# SCH_fateh_pre-charge_circuit0_draft1.net
KiCad netlist of a schematic drawn in EasyEDA
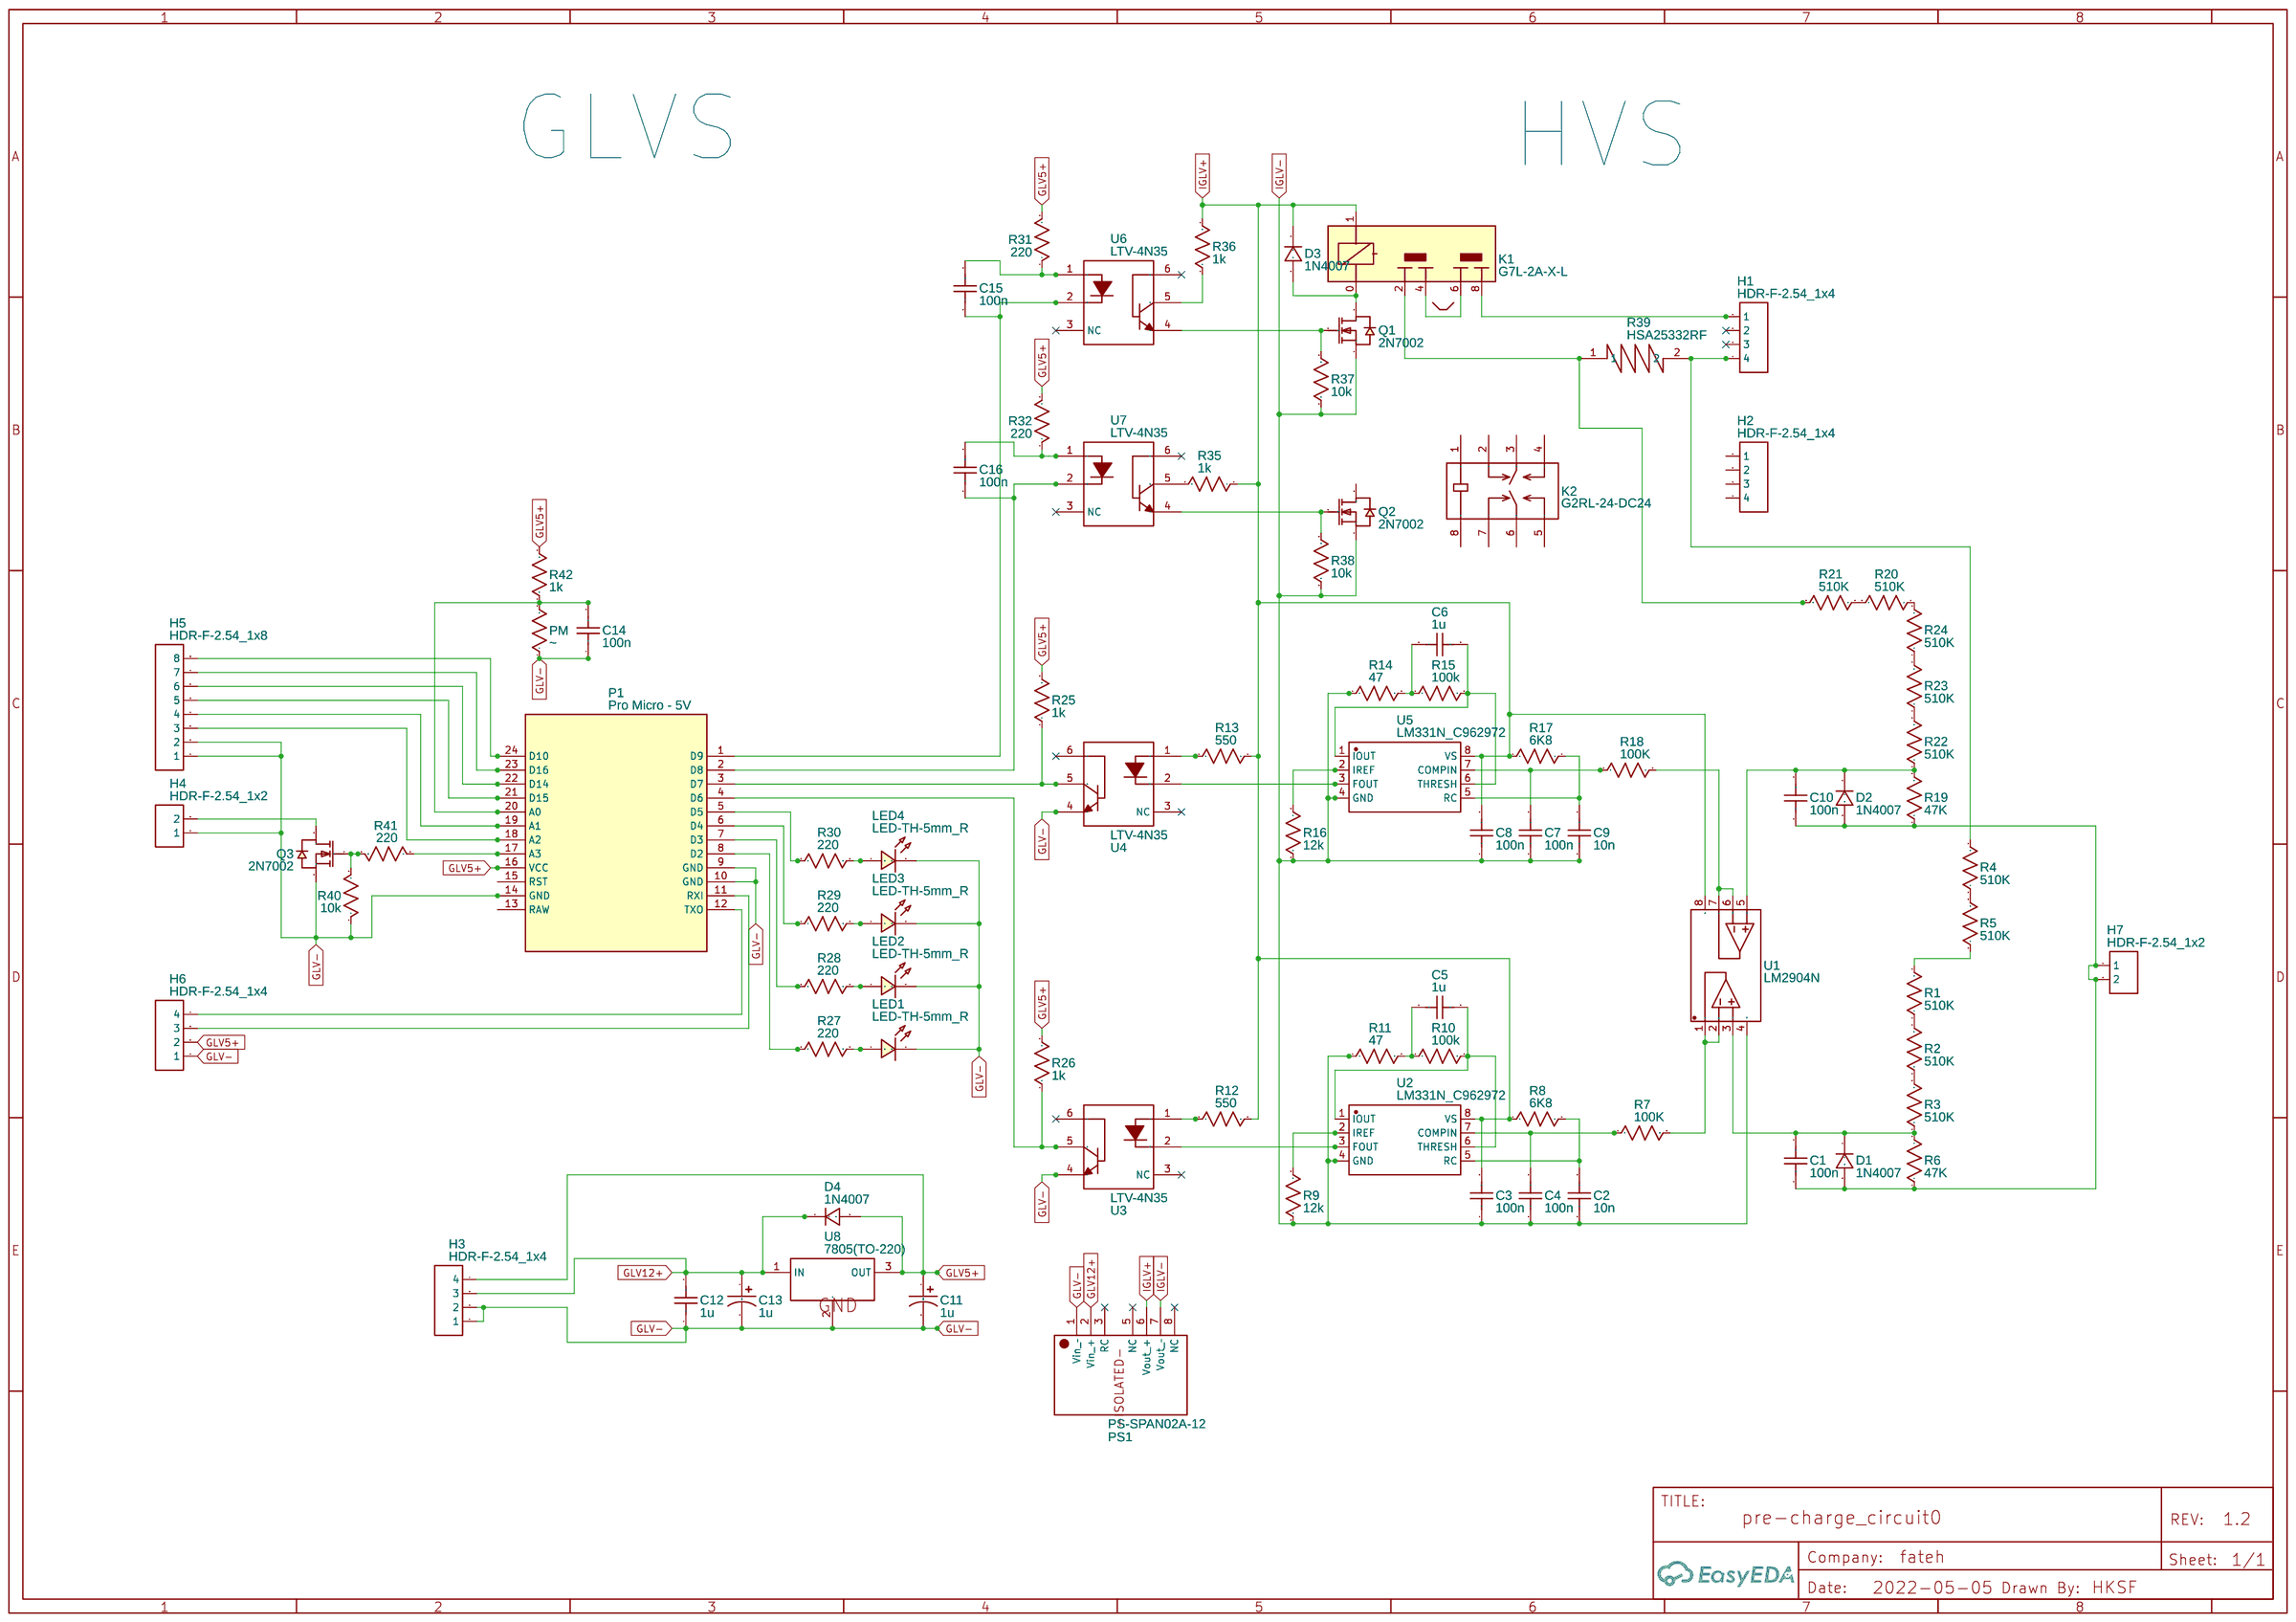
[diagram p0: schematic sheet]

(export (version "E")
  (design (tool "Eeschema 10.0.6"))
  (components
    (comp (ref "C1") (value "100n") (libsource (lib "") (part "C_RAD-0.1_US")))
    (comp (ref "C2") (value "10n") (libsource (lib "") (part "C_RAD-0.1_US")))
    (comp (ref "C3") (value "100n") (libsource (lib "") (part "C_RAD-0.1_US")))
    (comp (ref "C4") (value "100n") (libsource (lib "") (part "C_RAD-0.1_US")))
    (comp (ref "C5") (value "1u") (libsource (lib "") (part "C_RAD-0.1_US_1")))
    (comp (ref "C6") (value "1u") (libsource (lib "") (part "C_RAD-0.1_US_1")))
    (comp (ref "C7") (value "100n") (libsource (lib "") (part "C_RAD-0.1_US")))
    (comp (ref "C8") (value "100n") (libsource (lib "") (part "C_RAD-0.1_US")))
    (comp (ref "C9") (value "10n") (libsource (lib "") (part "C_RAD-0.1_US")))
    (comp (ref "C10") (value "100n") (libsource (lib "") (part "C_RAD-0.1_US")))
    (comp (ref "C11") (value "1u") (libsource (lib "") (part "CE_TH_D12.5×F5.0_US")))
    (comp (ref "C12") (value "1u") (libsource (lib "") (part "C_RAD-0.1_US")))
    (comp (ref "C13") (value "1u") (libsource (lib "") (part "CE_TH_D12.5×F5.0_US")))
    (comp (ref "C14") (value "100n") (libsource (lib "") (part "C_RAD-0.1_US")))
    (comp (ref "C15") (value "100n") (libsource (lib "") (part "C_RAD-0.1_US")))
    (comp (ref "C16") (value "100n") (libsource (lib "") (part "C_RAD-0.1_US")))
    (comp (ref "D1")
      (value "1N4007")
      (fields (field (name "BOM_Supplier Part") "C106903"))
      (libsource (lib "") (part "1N4007"))
    )
    (comp (ref "D2")
      (value "1N4007")
      (fields (field (name "BOM_Supplier Part") "C106903"))
      (libsource (lib "") (part "1N4007"))
    )
    (comp (ref "D3")
      (value "1N4007")
      (fields (field (name "BOM_Supplier Part") "C106903"))
      (libsource (lib "") (part "1N4007"))
    )
    (comp (ref "D4")
      (value "1N4007")
      (fields (field (name "BOM_Supplier Part") "C106903"))
      (libsource (lib "") (part "1N4007_1"))
    )
    (comp (ref "H1")
      (value "HDR-F-2.54_1x4")
      (fields (field (name "BOM_Supplier Part") "C225501"))
      (libsource (lib "") (part "HDR-F-2.54_1x4"))
    )
    (comp (ref "H2")
      (value "HDR-F-2.54_1x4")
      (fields (field (name "BOM_Supplier Part") "C225501"))
      (libsource (lib "") (part "HDR-F-2.54_1x4"))
    )
    (comp (ref "H3")
      (value "HDR-F-2.54_1x4")
      (fields (field (name "BOM_Supplier Part") "C225501"))
      (libsource (lib "") (part "HDR-F-2.54_1x4_1"))
    )
    (comp (ref "H4")
      (value "HDR-F-2.54_1x2")
      (fields (field (name "BOM_Supplier Part") "C49661"))
      (libsource (lib "") (part "HDR-F-2.54_1x2_1"))
    )
    (comp (ref "H5")
      (value "HDR-F-2.54_1x8")
      (fields (field (name "BOM_Supplier Part") "C225505"))
      (libsource (lib "") (part "HDR-F-2.54_1x8"))
    )
    (comp (ref "H6")
      (value "HDR-F-2.54_1x4")
      (fields (field (name "BOM_Supplier Part") "C225501"))
      (libsource (lib "") (part "HDR-F-2.54_1x4_1"))
    )
    (comp (ref "H7")
      (value "HDR-F-2.54_1x2")
      (fields (field (name "BOM_Supplier Part") "C49661"))
      (libsource (lib "") (part "HDR-F-2.54_1x2"))
    )
    (comp (ref "K1") (value "G7L-2A-X-L") (libsource (lib "") (part "G7L-2A-X-L")))
    (comp (ref "K2")
      (value "G2RL-24-DC24")
      (fields (field (name "BOM_Supplier Part") "C397256"))
      (libsource (lib "") (part "G2RL-24-DC24"))
    )
    (comp (ref "LED1")
      (value "LED-TH-5mm_R")
      (fields
        (field (name "BOM_Manufacturer Part") "333-2SURD/S530-A3")
        (field (name "BOM_Supplier Part") "C87271")
      )
      (libsource (lib "") (part "LED-TH-5mm_R"))
    )
    (comp (ref "LED2")
      (value "LED-TH-5mm_R")
      (fields
        (field (name "BOM_Manufacturer Part") "333-2SURD/S530-A3")
        (field (name "BOM_Supplier Part") "C87271")
      )
      (libsource (lib "") (part "LED-TH-5mm_R"))
    )
    (comp (ref "LED3")
      (value "LED-TH-5mm_R")
      (fields
        (field (name "BOM_Manufacturer Part") "333-2SURD/S530-A3")
        (field (name "BOM_Supplier Part") "C87271")
      )
      (libsource (lib "") (part "LED-TH-5mm_R"))
    )
    (comp (ref "LED4")
      (value "LED-TH-5mm_R")
      (fields
        (field (name "BOM_Manufacturer Part") "333-2SURD/S530-A3")
        (field (name "BOM_Supplier Part") "C87271")
      )
      (libsource (lib "") (part "LED-TH-5mm_R"))
    )
    (comp (ref "P1") (value "Pro Micro - 5V") (libsource (lib "") (part "Pro Micro - 5V")))
    (comp (ref "PM") (value "~") (libsource (lib "") (part "R_AXIAL-0.3_US_5")))
    (comp (ref "PS1")
      (value "PS-SPAN02A-12")
      (fields
        (field (name "BOM_Manufacturer Part") "SPAN02A-12")
        (field (name "BOM_Supplier Part") "709-SPAN02A-12")
      )
      (libsource (lib "") (part "PS-SPAN02A-12"))
    )
    (comp (ref "Q1")
      (value "2N7002")
      (fields (field (name "BOM_Manufacturer Part") "2N7002,215") (field (name "BOM_Supplier Part") "C65189"))
      (libsource (lib "") (part "2N7002"))
    )
    (comp (ref "Q2")
      (value "2N7002")
      (fields (field (name "BOM_Manufacturer Part") "2N7002,215") (field (name "BOM_Supplier Part") "C65189"))
      (libsource (lib "") (part "2N7002"))
    )
    (comp (ref "Q3")
      (value "2N7002")
      (fields (field (name "BOM_Manufacturer Part") "2N7002,215") (field (name "BOM_Supplier Part") "C65189"))
      (libsource (lib "") (part "2N7002_1"))
    )
    (comp (ref "R1") (value "510K") (libsource (lib "") (part "R_AXIAL-0.3_US_1")))
    (comp (ref "R2") (value "510K") (libsource (lib "") (part "R_AXIAL-0.3_US_1")))
    (comp (ref "R3") (value "510K") (libsource (lib "") (part "R_AXIAL-0.3_US_1")))
    (comp (ref "R4") (value "510K") (libsource (lib "") (part "R_AXIAL-0.3_US_1")))
    (comp (ref "R5") (value "510K") (libsource (lib "") (part "R_AXIAL-0.3_US_1")))
    (comp (ref "R6") (value "47K") (libsource (lib "") (part "R_AXIAL-0.3_US_1")))
    (comp (ref "R7") (value "100K") (libsource (lib "") (part "R_AXIAL-0.3_US")))
    (comp (ref "R8") (value "6K8") (libsource (lib "") (part "R_AXIAL-0.3_US")))
    (comp (ref "R9") (value "12k") (libsource (lib "") (part "R_AXIAL-0.3_US_1")))
    (comp (ref "R10") (value "100k") (libsource (lib "") (part "R_AXIAL-0.3_US")))
    (comp (ref "R11") (value "47") (libsource (lib "") (part "R_AXIAL-0.3_US")))
    (comp (ref "R12") (value "550") (libsource (lib "") (part "R_AXIAL-0.3_US")))
    (comp (ref "R13") (value "550") (libsource (lib "") (part "R_AXIAL-0.3_US")))
    (comp (ref "R14") (value "47") (libsource (lib "") (part "R_AXIAL-0.3_US")))
    (comp (ref "R15") (value "100k") (libsource (lib "") (part "R_AXIAL-0.3_US")))
    (comp (ref "R16") (value "12k") (libsource (lib "") (part "R_AXIAL-0.3_US_1")))
    (comp (ref "R17") (value "6K8") (libsource (lib "") (part "R_AXIAL-0.3_US")))
    (comp (ref "R18") (value "100K") (libsource (lib "") (part "R_AXIAL-0.3_US")))
    (comp (ref "R19") (value "47K") (libsource (lib "") (part "R_AXIAL-0.3_US_1")))
    (comp (ref "R20") (value "510K") (libsource (lib "") (part "R_AXIAL-0.3_US_3")))
    (comp (ref "R21") (value "510K") (libsource (lib "") (part "R_AXIAL-0.3_US_3")))
    (comp (ref "R22") (value "510K") (libsource (lib "") (part "R_AXIAL-0.3_US_1")))
    (comp (ref "R23") (value "510K") (libsource (lib "") (part "R_AXIAL-0.3_US_1")))
    (comp (ref "R24") (value "510K") (libsource (lib "") (part "R_AXIAL-0.3_US_1")))
    (comp (ref "R25") (value "1k") (libsource (lib "") (part "R_AXIAL-0.3_US_1")))
    (comp (ref "R26") (value "1k") (libsource (lib "") (part "R_AXIAL-0.3_US_1")))
    (comp (ref "R27") (value "220") (libsource (lib "") (part "R_AXIAL-0.3_US")))
    (comp (ref "R28") (value "220") (libsource (lib "") (part "R_AXIAL-0.3_US")))
    (comp (ref "R29") (value "220") (libsource (lib "") (part "R_AXIAL-0.3_US")))
    (comp (ref "R30") (value "220") (libsource (lib "") (part "R_AXIAL-0.3_US")))
    (comp (ref "R31") (value "220") (libsource (lib "") (part "R_AXIAL-0.3_US_2")))
    (comp (ref "R32") (value "220") (libsource (lib "") (part "R_AXIAL-0.3_US_2")))
    (comp (ref "R35") (value "1k") (libsource (lib "") (part "R_AXIAL-0.3_US_3")))
    (comp (ref "R36") (value "1k") (libsource (lib "") (part "R_AXIAL-0.3_US_1")))
    (comp (ref "R37") (value "10k") (libsource (lib "") (part "R_AXIAL-0.3_US_1")))
    (comp (ref "R38") (value "10k") (libsource (lib "") (part "R_AXIAL-0.3_US_1")))
    (comp (ref "R39") (value "HSA25332RF") (libsource (lib "") (part "HSA25332RF")))
    (comp (ref "R40") (value "10k") (libsource (lib "") (part "R_AXIAL-0.3_US_2")))
    (comp (ref "R41") (value "220") (libsource (lib "") (part "R_AXIAL-0.3_US_4")))
    (comp (ref "R42") (value "1k") (libsource (lib "") (part "R_AXIAL-0.3_US_1")))
    (comp (ref "U1")
      (value "LM2904N")
      (fields (field (name "BOM_Supplier Part") "C232852"))
      (libsource (lib "") (part "LM2904N"))
    )
    (comp (ref "U2")
      (value "LM331N_C962972")
      (fields (field (name "BOM_Manufacturer Part") "LM331N") (field (name "BOM_Supplier Part") "C962972"))
      (libsource (lib "") (part "LM331N_C962972"))
    )
    (comp (ref "U3")
      (value "LTV-4N35")
      (fields (field (name "BOM_Supplier Part") "C343878"))
      (libsource (lib "") (part "LTV-4N35"))
    )
    (comp (ref "U4")
      (value "LTV-4N35")
      (fields (field (name "BOM_Supplier Part") "C343878"))
      (libsource (lib "") (part "LTV-4N35"))
    )
    (comp (ref "U5")
      (value "LM331N_C962972")
      (fields (field (name "BOM_Manufacturer Part") "LM331N") (field (name "BOM_Supplier Part") "C962972"))
      (libsource (lib "") (part "LM331N_C962972"))
    )
    (comp (ref "U6")
      (value "LTV-4N35")
      (fields (field (name "BOM_Supplier Part") "C343878"))
      (libsource (lib "") (part "LTV-4N35_1"))
    )
    (comp (ref "U7")
      (value "LTV-4N35")
      (fields (field (name "BOM_Supplier Part") "C343878"))
      (libsource (lib "") (part "LTV-4N35_1"))
    )
    (comp (ref "U8")
      (value "7805(TO-220)")
      (fields (field (name "BOM_Manufacturer Part") "L7805CV-DG") (field (name "BOM_Supplier Part") "C3795"))
      (libsource (lib "") (part "7805(TO-220)"))
    )
  )
  (nets
    (net (code "1") (name "GLV-") (class "Default")
      (node (ref "C11") (pin "2") (pinfunction "2_2") (pintype "unspecified"))
      (node (ref "C12") (pin "1") (pinfunction "1_1") (pintype "unspecified"))
      (node (ref "C13") (pin "2") (pinfunction "2_2") (pintype "unspecified"))
      (node (ref "C14") (pin "1") (pinfunction "1_1") (pintype "unspecified"))
      (node (ref "H3") (pin "1") (pinfunction "1_1") (pintype "unspecified"))
      (node (ref "H3") (pin "2") (pinfunction "2_2") (pintype "unspecified"))
      (node (ref "H4") (pin "1") (pinfunction "1_1") (pintype "input"))
      (node (ref "H5") (pin "1") (pinfunction "1_1") (pintype "unspecified"))
      (node (ref "H5") (pin "2") (pinfunction "2_2") (pintype "unspecified"))
      (node (ref "H6") (pin "1") (pinfunction "1_1") (pintype "unspecified"))
      (node (ref "LED1") (pin "2") (pinfunction "2_2") (pintype "unspecified"))
      (node (ref "LED2") (pin "2") (pinfunction "2_2") (pintype "unspecified"))
      (node (ref "LED3") (pin "2") (pinfunction "2_2") (pintype "unspecified"))
      (node (ref "LED4") (pin "2") (pinfunction "2_2") (pintype "unspecified"))
      (node (ref "P1") (pin "10") (pinfunction "GND_10") (pintype "unspecified"))
      (node (ref "P1") (pin "14") (pinfunction "GND_14") (pintype "unspecified"))
      (node (ref "P1") (pin "9") (pinfunction "GND_9") (pintype "unspecified"))
      (node (ref "PM") (pin "1") (pinfunction "1_1") (pintype "unspecified"))
      (node (ref "PS1") (pin "1") (pinfunction "Vin_–_1") (pintype "unspecified"))
      (node (ref "Q3") (pin "2") (pinfunction "S_2") (pintype "unspecified"))
      (node (ref "R40") (pin "1") (pinfunction "1_1") (pintype "unspecified"))
      (node (ref "U3") (pin "4") (pinfunction "4_4") (pintype "unspecified"))
      (node (ref "U4") (pin "4") (pinfunction "4_4") (pintype "unspecified"))
      (node (ref "U8") (pin "2") (pinfunction "GND_2") (pintype "passive"))
    )
    (net (code "2") (name "GLV5+") (class "Default")
      (node (ref "C11") (pin "1") (pinfunction "1_1") (pintype "unspecified"))
      (node (ref "D4") (pin "2") (pinfunction "2_2") (pintype "unspecified"))
      (node (ref "H3") (pin "4") (pinfunction "4_4") (pintype "unspecified"))
      (node (ref "H6") (pin "2") (pinfunction "2_2") (pintype "unspecified"))
      (node (ref "P1") (pin "16") (pinfunction "VCC_16") (pintype "unspecified"))
      (node (ref "R25") (pin "2") (pinfunction "2_2") (pintype "unspecified"))
      (node (ref "R26") (pin "2") (pinfunction "2_2") (pintype "unspecified"))
      (node (ref "R31") (pin "2") (pinfunction "2_2") (pintype "unspecified"))
      (node (ref "R32") (pin "2") (pinfunction "2_2") (pintype "unspecified"))
      (node (ref "R42") (pin "2") (pinfunction "2_2") (pintype "unspecified"))
      (node (ref "U8") (pin "3") (pinfunction "OUT_3") (pintype "passive"))
    )
    (net (code "3") (name "GLV12+") (class "Default")
      (node (ref "C12") (pin "2") (pinfunction "2_2") (pintype "unspecified"))
      (node (ref "C13") (pin "1") (pinfunction "1_1") (pintype "unspecified"))
      (node (ref "D4") (pin "1") (pinfunction "1_1") (pintype "unspecified"))
      (node (ref "H3") (pin "3") (pinfunction "3_3") (pintype "unspecified"))
      (node (ref "PS1") (pin "2") (pinfunction "Vin_+_2") (pintype "unspecified"))
      (node (ref "U8") (pin "1") (pinfunction "IN_1") (pintype "passive"))
    )
    (net (code "4") (name "IGLV+") (class "Default")
      (node (ref "C3") (pin "2") (pinfunction "2_2") (pintype "unspecified"))
      (node (ref "C8") (pin "2") (pinfunction "2_2") (pintype "unspecified"))
      (node (ref "D3") (pin "1") (pinfunction "1_1") (pintype "unspecified"))
      (node (ref "K1") (pin "1") (pintype "unspecified"))
      (node (ref "PS1") (pin "6") (pinfunction "Vout_+_6") (pintype "unspecified"))
      (node (ref "R12") (pin "2") (pinfunction "2_2") (pintype "unspecified"))
      (node (ref "R13") (pin "2") (pinfunction "2_2") (pintype "unspecified"))
      (node (ref "R17") (pin "1") (pinfunction "1_1") (pintype "unspecified"))
      (node (ref "R35") (pin "1") (pinfunction "1_1") (pintype "unspecified"))
      (node (ref "R36") (pin "2") (pinfunction "2_2") (pintype "unspecified"))
      (node (ref "R8") (pin "1") (pinfunction "1_1") (pintype "unspecified"))
      (node (ref "U1") (pin "8") (pinfunction "+VS_8") (pintype "unspecified"))
      (node (ref "U2") (pin "8") (pinfunction "VS_8") (pintype "unspecified"))
      (node (ref "U5") (pin "8") (pinfunction "VS_8") (pintype "unspecified"))
    )
    (net (code "5") (name "IGLV-") (class "Default")
      (node (ref "C2") (pin "1") (pinfunction "1_1") (pintype "unspecified"))
      (node (ref "C3") (pin "1") (pinfunction "1_1") (pintype "unspecified"))
      (node (ref "C4") (pin "1") (pinfunction "1_1") (pintype "unspecified"))
      (node (ref "C7") (pin "1") (pinfunction "1_1") (pintype "unspecified"))
      (node (ref "C8") (pin "1") (pinfunction "1_1") (pintype "unspecified"))
      (node (ref "C9") (pin "1") (pinfunction "1_1") (pintype "unspecified"))
      (node (ref "PS1") (pin "7") (pinfunction "Vout_–_7") (pintype "unspecified"))
      (node (ref "Q1") (pin "2") (pinfunction "S_2") (pintype "unspecified"))
      (node (ref "Q2") (pin "2") (pinfunction "S_2") (pintype "unspecified"))
      (node (ref "R11") (pin "1") (pinfunction "1_1") (pintype "unspecified"))
      (node (ref "R14") (pin "1") (pinfunction "1_1") (pintype "unspecified"))
      (node (ref "R16") (pin "1") (pinfunction "1_1") (pintype "unspecified"))
      (node (ref "R37") (pin "1") (pinfunction "1_1") (pintype "unspecified"))
      (node (ref "R38") (pin "1") (pinfunction "1_1") (pintype "unspecified"))
      (node (ref "R9") (pin "1") (pinfunction "1_1") (pintype "unspecified"))
      (node (ref "U1") (pin "4") (pinfunction "-VS_4") (pintype "unspecified"))
      (node (ref "U2") (pin "4") (pinfunction "GND_4") (pintype "unspecified"))
      (node (ref "U5") (pin "4") (pinfunction "GND_4") (pintype "unspecified"))
    )
    (net (code "6") (name "Net-(C1-Pad1)") (class "Default")
      (node (ref "C1") (pin "1") (pinfunction "1_1") (pintype "unspecified"))
      (node (ref "C10") (pin "1") (pinfunction "1_1") (pintype "unspecified"))
      (node (ref "D1") (pin "2") (pinfunction "2_2") (pintype "unspecified"))
      (node (ref "D2") (pin "2") (pinfunction "2_2") (pintype "unspecified"))
      (node (ref "H7") (pin "1") (pinfunction "1_1") (pintype "input"))
      (node (ref "H7") (pin "2") (pinfunction "2_2") (pintype "input"))
      (node (ref "R19") (pin "1") (pinfunction "1_1") (pintype "unspecified"))
      (node (ref "R6") (pin "1") (pinfunction "1_1") (pintype "unspecified"))
    )
    (net (code "7") (name "Net-(C5-Pad1)") (class "Default")
      (node (ref "C5") (pin "1") (pinfunction "1_1") (pintype "unspecified"))
      (node (ref "R10") (pin "1") (pinfunction "1_1") (pintype "unspecified"))
      (node (ref "R11") (pin "2") (pinfunction "2_2") (pintype "unspecified"))
    )
    (net (code "8") (name "Net-(C6-Pad1)") (class "Default")
      (node (ref "C6") (pin "1") (pinfunction "1_1") (pintype "unspecified"))
      (node (ref "R14") (pin "2") (pinfunction "2_2") (pintype "unspecified"))
      (node (ref "R15") (pin "1") (pinfunction "1_1") (pintype "unspecified"))
    )
    (net (code "9") (name "Net-(C10-Pad2)") (class "Default")
      (node (ref "C10") (pin "2") (pinfunction "2_2") (pintype "unspecified"))
      (node (ref "D2") (pin "1") (pinfunction "1_1") (pintype "unspecified"))
      (node (ref "R19") (pin "2") (pinfunction "2_2") (pintype "unspecified"))
      (node (ref "R22") (pin "1") (pinfunction "1_1") (pintype "unspecified"))
      (node (ref "U1") (pin "5") (pinfunction "5_5") (pintype "unspecified"))
    )
    (net (code "10") (name "Net-(C15-Pad2)") (class "Default")
      (node (ref "C15") (pin "2") (pinfunction "2_2") (pintype "unspecified"))
      (node (ref "R31") (pin "1") (pinfunction "1_1") (pintype "unspecified"))
      (node (ref "U6") (pin "1") (pinfunction "1_1") (pintype "unspecified"))
    )
    (net (code "11") (name "Net-(C16-Pad2)") (class "Default")
      (node (ref "C16") (pin "2") (pinfunction "2_2") (pintype "unspecified"))
      (node (ref "R32") (pin "1") (pinfunction "1_1") (pintype "unspecified"))
      (node (ref "U7") (pin "1") (pinfunction "1_1") (pintype "unspecified"))
    )
    (net (code "12") (name "Net-(H1-Pad1)") (class "Default")
      (node (ref "H1") (pin "1") (pinfunction "1_1") (pintype "unspecified"))
      (node (ref "K1") (pin "8") (pintype "unspecified"))
    )
    (net (code "13") (name "Net-(H1-Pad4)") (class "Default")
      (node (ref "H1") (pin "4") (pinfunction "4_4") (pintype "unspecified"))
      (node (ref "R39") (pin "2") (pinfunction "2_2") (pintype "unspecified"))
      (node (ref "R4") (pin "2") (pinfunction "2_2") (pintype "unspecified"))
    )
    (net (code "14") (name "Net-(K1-Pad2)") (class "Default")
      (node (ref "K1") (pin "2") (pintype "unspecified"))
      (node (ref "R21") (pin "2") (pinfunction "2_2") (pintype "unspecified"))
      (node (ref "R39") (pin "1") (pinfunction "1_1") (pintype "unspecified"))
    )
    (net (code "15") (name "Net-(K1-Pad4)") (class "Default")
      (node (ref "K1") (pin "4") (pintype "unspecified"))
      (node (ref "K1") (pin "6") (pintype "unspecified"))
    )
    (net (code "16") (name "Net-(LED1-Pad1)") (class "Default")
      (node (ref "LED1") (pin "1") (pinfunction "1_1") (pintype "unspecified"))
      (node (ref "R27") (pin "2") (pinfunction "2_2") (pintype "unspecified"))
    )
    (net (code "17") (name "Net-(LED2-Pad1)") (class "Default")
      (node (ref "LED2") (pin "1") (pinfunction "1_1") (pintype "unspecified"))
      (node (ref "R28") (pin "2") (pinfunction "2_2") (pintype "unspecified"))
    )
    (net (code "18") (name "Net-(LED3-Pad1)") (class "Default")
      (node (ref "LED3") (pin "1") (pinfunction "1_1") (pintype "unspecified"))
      (node (ref "R29") (pin "2") (pinfunction "2_2") (pintype "unspecified"))
    )
    (net (code "19") (name "Net-(LED4-Pad1)") (class "Default")
      (node (ref "LED4") (pin "1") (pinfunction "1_1") (pintype "unspecified"))
      (node (ref "R30") (pin "2") (pinfunction "2_2") (pintype "unspecified"))
    )
    (net (code "20") (name "Net-(P1-A0)") (class "Default")
      (node (ref "C14") (pin "2") (pinfunction "2_2") (pintype "unspecified"))
      (node (ref "P1") (pin "20") (pinfunction "A0_20") (pintype "unspecified"))
      (node (ref "PM") (pin "2") (pinfunction "2_2") (pintype "unspecified"))
      (node (ref "R42") (pin "1") (pinfunction "1_1") (pintype "unspecified"))
    )
    (net (code "21") (name "Net-(P1-A1)") (class "Default")
      (node (ref "H5") (pin "4") (pinfunction "4_4") (pintype "unspecified"))
      (node (ref "P1") (pin "19") (pinfunction "A1_19") (pintype "unspecified"))
    )
    (net (code "22") (name "Net-(P1-A2)") (class "Default")
      (node (ref "H5") (pin "3") (pinfunction "3_3") (pintype "unspecified"))
      (node (ref "P1") (pin "18") (pinfunction "A2_18") (pintype "unspecified"))
    )
    (net (code "23") (name "Net-(P1-A3)") (class "Default")
      (node (ref "P1") (pin "17") (pinfunction "A3_17") (pintype "unspecified"))
      (node (ref "R41") (pin "1") (pinfunction "1_1") (pintype "unspecified"))
    )
    (net (code "24") (name "Net-(P1-D2)") (class "Default")
      (node (ref "P1") (pin "8") (pinfunction "D2_8") (pintype "unspecified"))
      (node (ref "R27") (pin "1") (pinfunction "1_1") (pintype "unspecified"))
    )
    (net (code "25") (name "Net-(P1-D3)") (class "Default")
      (node (ref "P1") (pin "7") (pinfunction "D3_7") (pintype "unspecified"))
      (node (ref "R28") (pin "1") (pinfunction "1_1") (pintype "unspecified"))
    )
    (net (code "26") (name "Net-(P1-D4)") (class "Default")
      (node (ref "P1") (pin "6") (pinfunction "D4_6") (pintype "unspecified"))
      (node (ref "R29") (pin "1") (pinfunction "1_1") (pintype "unspecified"))
    )
    (net (code "27") (name "Net-(P1-D5)") (class "Default")
      (node (ref "P1") (pin "5") (pinfunction "D5_5") (pintype "unspecified"))
      (node (ref "R30") (pin "1") (pinfunction "1_1") (pintype "unspecified"))
    )
    (net (code "28") (name "Net-(P1-D6)") (class "Default")
      (node (ref "P1") (pin "4") (pinfunction "D6_4") (pintype "unspecified"))
      (node (ref "R26") (pin "1") (pinfunction "1_1") (pintype "unspecified"))
      (node (ref "U3") (pin "5") (pinfunction "5_5") (pintype "unspecified"))
    )
    (net (code "29") (name "Net-(P1-D7)") (class "Default")
      (node (ref "P1") (pin "3") (pinfunction "D7_3") (pintype "unspecified"))
      (node (ref "R25") (pin "1") (pinfunction "1_1") (pintype "unspecified"))
      (node (ref "U4") (pin "5") (pinfunction "5_5") (pintype "unspecified"))
    )
    (net (code "30") (name "Net-(P1-D8)") (class "Default")
      (node (ref "C16") (pin "1") (pinfunction "1_1") (pintype "unspecified"))
      (node (ref "P1") (pin "2") (pinfunction "D8_2") (pintype "unspecified"))
      (node (ref "U7") (pin "2") (pinfunction "2_2") (pintype "unspecified"))
    )
    (net (code "31") (name "Net-(P1-D9)") (class "Default")
      (node (ref "C15") (pin "1") (pinfunction "1_1") (pintype "unspecified"))
      (node (ref "P1") (pin "1") (pinfunction "D9_1") (pintype "unspecified"))
      (node (ref "U6") (pin "2") (pinfunction "2_2") (pintype "unspecified"))
    )
    (net (code "32") (name "Net-(P1-D10)") (class "Default")
      (node (ref "H5") (pin "8") (pinfunction "8_8") (pintype "unspecified"))
      (node (ref "P1") (pin "24") (pinfunction "D10_24") (pintype "unspecified"))
    )
    (net (code "33") (name "Net-(P1-D14)") (class "Default")
      (node (ref "H5") (pin "6") (pinfunction "6_6") (pintype "unspecified"))
      (node (ref "P1") (pin "22") (pinfunction "D14_22") (pintype "unspecified"))
    )
    (net (code "34") (name "Net-(P1-D15)") (class "Default")
      (node (ref "H5") (pin "5") (pinfunction "5_5") (pintype "unspecified"))
      (node (ref "P1") (pin "21") (pinfunction "D15_21") (pintype "unspecified"))
    )
    (net (code "35") (name "Net-(P1-D16)") (class "Default")
      (node (ref "H5") (pin "7") (pinfunction "7_7") (pintype "unspecified"))
      (node (ref "P1") (pin "23") (pinfunction "D16_23") (pintype "unspecified"))
    )
    (net (code "36") (name "Net-(P1-RXI)") (class "Default")
      (node (ref "H6") (pin "3") (pinfunction "3_3") (pintype "unspecified"))
      (node (ref "P1") (pin "11") (pinfunction "RXI_11") (pintype "unspecified"))
    )
    (net (code "37") (name "Net-(P1-TXO)") (class "Default")
      (node (ref "H6") (pin "4") (pinfunction "4_4") (pintype "unspecified"))
      (node (ref "P1") (pin "12") (pinfunction "TXO_12") (pintype "unspecified"))
    )
    (net (code "38") (name "Net-(Q1-D)") (class "Default")
      (node (ref "D3") (pin "2") (pinfunction "2_2") (pintype "unspecified"))
      (node (ref "K1") (pin "0") (pintype "unspecified"))
      (node (ref "Q1") (pin "3") (pinfunction "D_3") (pintype "unspecified"))
    )
    (net (code "39") (name "Net-(Q1-G)") (class "Default")
      (node (ref "Q1") (pin "1") (pinfunction "G_1") (pintype "unspecified"))
      (node (ref "R37") (pin "2") (pinfunction "2_2") (pintype "unspecified"))
      (node (ref "U6") (pin "4") (pinfunction "4_4") (pintype "unspecified"))
    )
    (net (code "40") (name "Net-(Q2-G)") (class "Default")
      (node (ref "Q2") (pin "1") (pinfunction "G_1") (pintype "unspecified"))
      (node (ref "R38") (pin "2") (pinfunction "2_2") (pintype "unspecified"))
      (node (ref "U7") (pin "4") (pinfunction "4_4") (pintype "unspecified"))
    )
    (net (code "41") (name "Net-(Q3-D)") (class "Default")
      (node (ref "H4") (pin "2") (pinfunction "2_2") (pintype "input"))
      (node (ref "Q3") (pin "3") (pinfunction "D_3") (pintype "unspecified"))
    )
    (net (code "42") (name "Net-(Q3-G)") (class "Default")
      (node (ref "Q3") (pin "1") (pinfunction "G_1") (pintype "unspecified"))
      (node (ref "R40") (pin "2") (pinfunction "2_2") (pintype "unspecified"))
      (node (ref "R41") (pin "2") (pinfunction "2_2") (pintype "unspecified"))
    )
    (net (code "43") (name "Net-(R1-Pad1)") (class "Default")
      (node (ref "R1") (pin "1") (pinfunction "1_1") (pintype "unspecified"))
      (node (ref "R2") (pin "2") (pinfunction "2_2") (pintype "unspecified"))
    )
    (net (code "44") (name "Net-(R1-Pad2)") (class "Default")
      (node (ref "R1") (pin "2") (pinfunction "2_2") (pintype "unspecified"))
      (node (ref "R5") (pin "1") (pinfunction "1_1") (pintype "unspecified"))
    )
    (net (code "45") (name "Net-(R2-Pad1)") (class "Default")
      (node (ref "R2") (pin "1") (pinfunction "1_1") (pintype "unspecified"))
      (node (ref "R3") (pin "2") (pinfunction "2_2") (pintype "unspecified"))
    )
    (net (code "46") (name "Net-(R4-Pad1)") (class "Default")
      (node (ref "R4") (pin "1") (pinfunction "1_1") (pintype "unspecified"))
      (node (ref "R5") (pin "2") (pinfunction "2_2") (pintype "unspecified"))
    )
    (net (code "47") (name "Net-(R7-Pad2)") (class "Default")
      (node (ref "R7") (pin "2") (pinfunction "2_2") (pintype "unspecified"))
      (node (ref "U1") (pin "1") (pinfunction "1_1") (pintype "unspecified"))
      (node (ref "U1") (pin "2") (pinfunction "2_2") (pintype "unspecified"))
    )
    (net (code "48") (name "Net-(R12-Pad1)") (class "Default")
      (node (ref "R12") (pin "1") (pinfunction "1_1") (pintype "unspecified"))
      (node (ref "U3") (pin "1") (pinfunction "1_1") (pintype "unspecified"))
    )
    (net (code "49") (name "Net-(R13-Pad1)") (class "Default")
      (node (ref "R13") (pin "1") (pinfunction "1_1") (pintype "unspecified"))
      (node (ref "U4") (pin "1") (pinfunction "1_1") (pintype "unspecified"))
    )
    (net (code "50") (name "Net-(R18-Pad2)") (class "Default")
      (node (ref "R18") (pin "2") (pinfunction "2_2") (pintype "unspecified"))
      (node (ref "U1") (pin "6") (pinfunction "6_6") (pintype "unspecified"))
      (node (ref "U1") (pin "7") (pinfunction "7_7") (pintype "unspecified"))
    )
    (net (code "51") (name "Net-(R20-Pad1)") (class "Default")
      (node (ref "R20") (pin "1") (pinfunction "1_1") (pintype "unspecified"))
      (node (ref "R24") (pin "2") (pinfunction "2_2") (pintype "unspecified"))
    )
    (net (code "52") (name "Net-(R20-Pad2)") (class "Default")
      (node (ref "R20") (pin "2") (pinfunction "2_2") (pintype "unspecified"))
      (node (ref "R21") (pin "1") (pinfunction "1_1") (pintype "unspecified"))
    )
    (net (code "53") (name "Net-(R22-Pad2)") (class "Default")
      (node (ref "R22") (pin "2") (pinfunction "2_2") (pintype "unspecified"))
      (node (ref "R23") (pin "1") (pinfunction "1_1") (pintype "unspecified"))
    )
    (net (code "54") (name "Net-(R23-Pad2)") (class "Default")
      (node (ref "R23") (pin "2") (pinfunction "2_2") (pintype "unspecified"))
      (node (ref "R24") (pin "1") (pinfunction "1_1") (pintype "unspecified"))
    )
    (net (code "55") (name "Net-(R35-Pad2)") (class "Default")
      (node (ref "R35") (pin "2") (pinfunction "2_2") (pintype "unspecified"))
      (node (ref "U7") (pin "5") (pinfunction "5_5") (pintype "unspecified"))
    )
    (net (code "56") (name "Net-(R36-Pad1)") (class "Default")
      (node (ref "R36") (pin "1") (pinfunction "1_1") (pintype "unspecified"))
      (node (ref "U6") (pin "5") (pinfunction "5_5") (pintype "unspecified"))
    )
    (net (code "57") (name "Net-(U1-VDD)") (class "Default")
      (node (ref "C1") (pin "2") (pinfunction "2_2") (pintype "unspecified"))
      (node (ref "D1") (pin "1") (pinfunction "1_1") (pintype "unspecified"))
      (node (ref "R3") (pin "1") (pinfunction "1_1") (pintype "unspecified"))
      (node (ref "R6") (pin "2") (pinfunction "2_2") (pintype "unspecified"))
      (node (ref "U1") (pin "3") (pinfunction "VDD_3") (pintype "unspecified"))
    )
    (net (code "58") (name "Net-(U2-COMPIN)") (class "Default")
      (node (ref "C4") (pin "2") (pinfunction "2_2") (pintype "unspecified"))
      (node (ref "R7") (pin "1") (pinfunction "1_1") (pintype "unspecified"))
      (node (ref "U2") (pin "7") (pinfunction "COMPIN_7") (pintype "unspecified"))
    )
    (net (code "59") (name "Net-(U2-FOUT)") (class "Default")
      (node (ref "U2") (pin "3") (pinfunction "FOUT_3") (pintype "unspecified"))
      (node (ref "U3") (pin "2") (pinfunction "2_2") (pintype "unspecified"))
    )
    (net (code "60") (name "Net-(U2-IOUT)") (class "Default")
      (node (ref "C5") (pin "2") (pinfunction "2_2") (pintype "unspecified"))
      (node (ref "R10") (pin "2") (pinfunction "2_2") (pintype "unspecified"))
      (node (ref "U2") (pin "1") (pinfunction "IOUT_1") (pintype "unspecified"))
      (node (ref "U2") (pin "6") (pinfunction "THRESH_6") (pintype "unspecified"))
    )
    (net (code "61") (name "Net-(U2-IREF)") (class "Default")
      (node (ref "R9") (pin "2") (pinfunction "2_2") (pintype "unspecified"))
      (node (ref "U2") (pin "2") (pinfunction "IREF_2") (pintype "unspecified"))
    )
    (net (code "62") (name "Net-(U2-RC)") (class "Default")
      (node (ref "C2") (pin "2") (pinfunction "2_2") (pintype "unspecified"))
      (node (ref "R8") (pin "2") (pinfunction "2_2") (pintype "unspecified"))
      (node (ref "U2") (pin "5") (pinfunction "RC_5") (pintype "unspecified"))
    )
    (net (code "63") (name "Net-(U5-COMPIN)") (class "Default")
      (node (ref "C7") (pin "2") (pinfunction "2_2") (pintype "unspecified"))
      (node (ref "R18") (pin "1") (pinfunction "1_1") (pintype "unspecified"))
      (node (ref "U5") (pin "7") (pinfunction "COMPIN_7") (pintype "unspecified"))
    )
    (net (code "64") (name "Net-(U5-FOUT)") (class "Default")
      (node (ref "U4") (pin "2") (pinfunction "2_2") (pintype "unspecified"))
      (node (ref "U5") (pin "3") (pinfunction "FOUT_3") (pintype "unspecified"))
    )
    (net (code "65") (name "Net-(U5-IOUT)") (class "Default")
      (node (ref "C6") (pin "2") (pinfunction "2_2") (pintype "unspecified"))
      (node (ref "R15") (pin "2") (pinfunction "2_2") (pintype "unspecified"))
      (node (ref "U5") (pin "1") (pinfunction "IOUT_1") (pintype "unspecified"))
      (node (ref "U5") (pin "6") (pinfunction "THRESH_6") (pintype "unspecified"))
    )
    (net (code "66") (name "Net-(U5-IREF)") (class "Default")
      (node (ref "R16") (pin "2") (pinfunction "2_2") (pintype "unspecified"))
      (node (ref "U5") (pin "2") (pinfunction "IREF_2") (pintype "unspecified"))
    )
    (net (code "67") (name "Net-(U5-RC)") (class "Default")
      (node (ref "C9") (pin "2") (pinfunction "2_2") (pintype "unspecified"))
      (node (ref "R17") (pin "2") (pinfunction "2_2") (pintype "unspecified"))
      (node (ref "U5") (pin "5") (pinfunction "RC_5") (pintype "unspecified"))
    )
    (net (code "68") (name "unconnected-(H1-Pad2)") (class "Default")
      (node (ref "H1") (pin "2") (pinfunction "2_2") (pintype "unspecified+no_connect"))
    )
    (net (code "69") (name "unconnected-(H1-Pad3)") (class "Default")
      (node (ref "H1") (pin "3") (pinfunction "3_3") (pintype "unspecified+no_connect"))
    )
    (net (code "70") (name "unconnected-(H2-Pad1)") (class "Default")
      (node (ref "H2") (pin "1") (pinfunction "1_1") (pintype "unspecified"))
    )
    (net (code "71") (name "unconnected-(H2-Pad2)") (class "Default")
      (node (ref "H2") (pin "2") (pinfunction "2_2") (pintype "unspecified"))
    )
    (net (code "72") (name "unconnected-(H2-Pad3)") (class "Default")
      (node (ref "H2") (pin "3") (pinfunction "3_3") (pintype "unspecified"))
    )
    (net (code "73") (name "unconnected-(H2-Pad4)") (class "Default")
      (node (ref "H2") (pin "4") (pinfunction "4_4") (pintype "unspecified"))
    )
    (net (code "74") (name "unconnected-(K2-Pad1)") (class "Default")
      (node (ref "K2") (pin "1") (pinfunction "1_1") (pintype "unspecified"))
    )
    (net (code "75") (name "unconnected-(K2-Pad2)") (class "Default")
      (node (ref "K2") (pin "2") (pinfunction "2_2") (pintype "unspecified"))
    )
    (net (code "76") (name "unconnected-(K2-Pad3)") (class "Default")
      (node (ref "K2") (pin "3") (pinfunction "3_3") (pintype "unspecified"))
    )
    (net (code "77") (name "unconnected-(K2-Pad4)") (class "Default")
      (node (ref "K2") (pin "4") (pinfunction "4_4") (pintype "unspecified"))
    )
    (net (code "78") (name "unconnected-(K2-Pad5)") (class "Default")
      (node (ref "K2") (pin "5") (pinfunction "5_5") (pintype "unspecified"))
    )
    (net (code "79") (name "unconnected-(K2-Pad6)") (class "Default")
      (node (ref "K2") (pin "6") (pinfunction "6_6") (pintype "unspecified"))
    )
    (net (code "80") (name "unconnected-(K2-Pad7)") (class "Default")
      (node (ref "K2") (pin "7") (pinfunction "7_7") (pintype "unspecified"))
    )
    (net (code "81") (name "unconnected-(K2-Pad8)") (class "Default")
      (node (ref "K2") (pin "8") (pinfunction "8_8") (pintype "unspecified"))
    )
    (net (code "82") (name "unconnected-(P1-RAW-Pad13)") (class "Default")
      (node (ref "P1") (pin "13") (pinfunction "RAW_13") (pintype "unspecified"))
    )
    (net (code "83") (name "unconnected-(P1-RST-Pad15)") (class "Default")
      (node (ref "P1") (pin "15") (pinfunction "RST_15") (pintype "unspecified"))
    )
    (net (code "84") (name "unconnected-(PS1-NC-Pad5)") (class "Default")
      (node (ref "PS1") (pin "5") (pinfunction "NC_5") (pintype "unspecified+no_connect"))
    )
    (net (code "85") (name "unconnected-(PS1-NC-Pad8)") (class "Default")
      (node (ref "PS1") (pin "8") (pinfunction "NC_8") (pintype "unspecified+no_connect"))
    )
    (net (code "86") (name "unconnected-(PS1-RC-Pad3)") (class "Default")
      (node (ref "PS1") (pin "3") (pinfunction "RC_3") (pintype "unspecified+no_connect"))
    )
    (net (code "87") (name "unconnected-(Q2-D-Pad3)") (class "Default")
      (node (ref "Q2") (pin "3") (pinfunction "D_3") (pintype "unspecified"))
    )
    (net (code "88") (name "unconnected-(U3-B-Pad6)") (class "Default")
      (node (ref "U3") (pin "6") (pinfunction "B_6") (pintype "unspecified+no_connect"))
    )
    (net (code "89") (name "unconnected-(U3-NC-Pad3)") (class "Default")
      (node (ref "U3") (pin "3") (pinfunction "NC_3") (pintype "unspecified+no_connect"))
    )
    (net (code "90") (name "unconnected-(U4-B-Pad6)") (class "Default")
      (node (ref "U4") (pin "6") (pinfunction "B_6") (pintype "unspecified+no_connect"))
    )
    (net (code "91") (name "unconnected-(U4-NC-Pad3)") (class "Default")
      (node (ref "U4") (pin "3") (pinfunction "NC_3") (pintype "unspecified+no_connect"))
    )
    (net (code "92") (name "unconnected-(U6-B-Pad6)") (class "Default")
      (node (ref "U6") (pin "6") (pinfunction "B_6") (pintype "unspecified+no_connect"))
    )
    (net (code "93") (name "unconnected-(U6-NC-Pad3)") (class "Default")
      (node (ref "U6") (pin "3") (pinfunction "NC_3") (pintype "unspecified+no_connect"))
    )
    (net (code "94") (name "unconnected-(U7-B-Pad6)") (class "Default")
      (node (ref "U7") (pin "6") (pinfunction "B_6") (pintype "unspecified+no_connect"))
    )
    (net (code "95") (name "unconnected-(U7-NC-Pad3)") (class "Default")
      (node (ref "U7") (pin "3") (pinfunction "NC_3") (pintype "unspecified+no_connect"))
    )
  )
)
